# SH1_-_POWER.net
KiCad netlist of a schematic drawn in Altium Designer
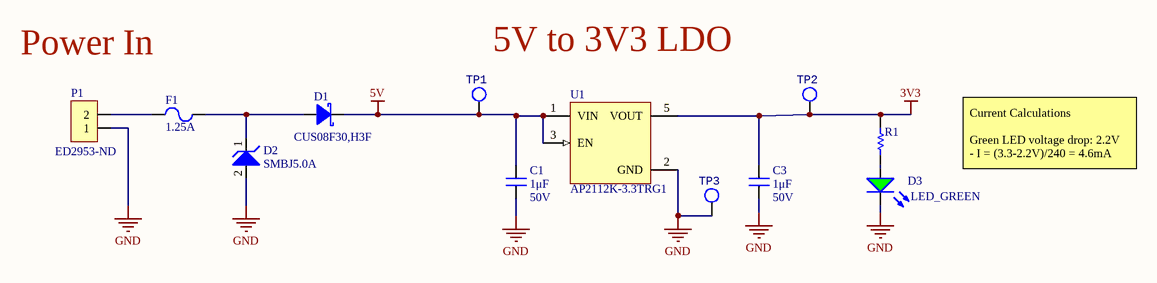
[diagram p0: SH1 - POWER.SchDoc]

(export (version "E")
  (design (tool "Eeschema 10.0.6"))
  (components
    (comp (ref "C1")
      (value "1μF")
      (footprint "CAP2012")
      (description "CAP CER 1UF 50V X7R 0805")
      (fields
        (field (name "VOLTAGE RATING") "50V")
        (field (name "LCSC PART #") "C28323")
        (field (name "Comment") "CAP_1uF_50V_0805")
      )
      (libsource (lib "UWRT_Schematic_Library_2020") (part "CAP_1uF_50V_0805"))
    )
    (comp (ref "C3")
      (value "1μF")
      (footprint "CAP2012")
      (description "CAP CER 1UF 50V X7R 0805")
      (fields
        (field (name "VOLTAGE RATING") "50V")
        (field (name "LCSC PART #") "C28323")
        (field (name "Comment") "CAP_1uF_50V_0805")
      )
      (libsource (lib "UWRT_Schematic_Library_2020") (part "CAP_1uF_50V_0805"))
    )
    (comp (ref "D1")
      (value "DIO_SCHOTTKY_30V_800mA")
      (footprint "SOD-323_UNIDIR")
      (description "DIODE SCHOTTKY 30V 800MA USC")
      (fields (field (name "MANUFACTURER PART NUMBER 1") "CUS08F30,H3F"))
      (libsource (lib "UWRT_Schematic_Library_2020") (part "DIO_SCHOTTKY_30V_800mA"))
    )
    (comp (ref "D2")
      (value "TVS_DIODE_UNIDIR_5V")
      (footprint "SMBJ5.0A")
      (description "TVS DIODE 5V 9.2V SMB")
      (fields (field (name "MANUFACTURER PART NUMBER 1") "SMBJ5.0A"))
      (libsource (lib "UWRT_Schematic_Library_2020") (part "TVS_DIODE_UNIDIR_5V"))
    )
    (comp (ref "D3")
      (value "LED_GREEN")
      (footprint "LED_0805_GREEN")
      (description "LED GREEN DIFFUSED 0805 SMD")
      (libsource (lib "UWRT_Schematic_Library_2020") (part "LED_GREEN"))
    )
    (comp (ref "F1")
      (value "FUSE_1.25A_1206")
      (footprint "FUSE_1206")
      (description "FUSE BOARD MOUNT 1.25A 63VAC/VDC 1206")
      (fields (field (name "CURRENT RATING") "1.25A"))
      (libsource (lib "UWRT_Schematic_Library_2020") (part "FUSE_1.25A_1206"))
    )
    (comp (ref "P1")
      (value "CONN_TERMINAL_2")
      (footprint "OSTYK51102030")
      (description "Header, 2-Pin")
      (fields (field (name "SUPPLIER PART NUMBER 1") "ED2953-ND"))
      (libsource (lib "UWRT_Schematic_Library_2020") (part "CONN_TERMINAL_2"))
    )
    (comp (ref "R1")
      (value "240")
      (footprint "RESC0805")
      (description "RES 240 OHM 1% 1/8W 0805")
      (libsource (lib "UWRT_Schematic_Library_2020") (part "RES_240Ω_0805_1%"))
    )
    (comp (ref "TP1")
      (value "TESTPOINT_LOOP")
      (footprint "TESTPOINT_LOOP")
      (description "TESTPOINT THRUHOLE")
      (libsource (lib "UWRT_Schematic_Library_2020") (part "TESTPOINT_LOOP"))
    )
    (comp (ref "TP2")
      (value "TESTPOINT_LOOP")
      (footprint "TESTPOINT_LOOP")
      (description "TESTPOINT THRUHOLE")
      (libsource (lib "UWRT_Schematic_Library_2020") (part "TESTPOINT_LOOP"))
    )
    (comp (ref "TP3")
      (value "TESTPOINT_LOOP")
      (footprint "TESTPOINT_LOOP")
      (description "TESTPOINT THRUHOLE")
      (libsource (lib "UWRT_Schematic_Library_2020") (part "TESTPOINT_LOOP"))
    )
    (comp (ref "U1")
      (value "LDO_3.3V_600mA")
      (footprint "SOT95P285X140-5N")
      (description "IC REG LINEAR 3.3V 600MA SOT25")
      (fields
        (field (name "MANUFACTURER PART NUMBER 1") "AP2112K-3.3TRG1")
        (field (name "LCSC PART #") "C51118")
      )
      (libsource (lib "UWRT_Schematic_Library_2020") (part "LDO_3.3V_600mA"))
    )
  )
  (nets
    (net (code "1") (name "3V3") (class "Default")
      (node (ref "C3") (pin "1") (pinfunction "1_1") (pintype "passive"))
      (node (ref "R1") (pin "2") (pinfunction "2_2") (pintype "passive"))
      (node (ref "TP2") (pin "1") (pintype "passive"))
      (node (ref "U1") (pin "5") (pinfunction "VOUT_5") (pintype "power_in"))
    )
    (net (code "2") (name "5V") (class "Default")
      (node (ref "C1") (pin "1") (pinfunction "1_1") (pintype "passive"))
      (node (ref "D1") (pin "2") (pinfunction "Cathode_2") (pintype "passive"))
      (node (ref "TP1") (pin "1") (pintype "passive"))
      (node (ref "U1") (pin "1") (pinfunction "VIN_1") (pintype "power_in"))
      (node (ref "U1") (pin "3") (pinfunction "EN_3") (pintype "input"))
    )
    (net (code "3") (name "GND") (class "Default")
      (node (ref "C1") (pin "2") (pinfunction "2_2") (pintype "passive"))
      (node (ref "C3") (pin "2") (pinfunction "2_2") (pintype "passive"))
      (node (ref "D2") (pin "2") (pinfunction "2_2") (pintype "passive"))
      (node (ref "D3") (pin "2") (pinfunction "K_2") (pintype "passive"))
      (node (ref "P1") (pin "1") (pinfunction "1_1") (pintype "passive"))
      (node (ref "TP3") (pin "1") (pintype "passive"))
      (node (ref "U1") (pin "2") (pinfunction "GND_2") (pintype "power_in"))
    )
    (net (code "4") (name "Net-(D1-Anode)") (class "Default")
      (node (ref "D1") (pin "1") (pinfunction "Anode_1") (pintype "passive"))
      (node (ref "D2") (pin "1") (pinfunction "1_1") (pintype "passive"))
      (node (ref "F1") (pin "2") (pinfunction "2_2") (pintype "passive"))
    )
    (net (code "5") (name "Net-(D3-A)") (class "Default")
      (node (ref "D3") (pin "1") (pinfunction "A_1") (pintype "passive"))
      (node (ref "R1") (pin "1") (pinfunction "1_1") (pintype "passive"))
    )
    (net (code "6") (name "Net-(F1-Pad1)") (class "Default")
      (node (ref "F1") (pin "1") (pinfunction "1_1") (pintype "passive"))
      (node (ref "P1") (pin "2") (pinfunction "2_2") (pintype "passive"))
    )
  )
)
